# v0_6_1.net
KiCad netlist of a schematic drawn in EAGLE
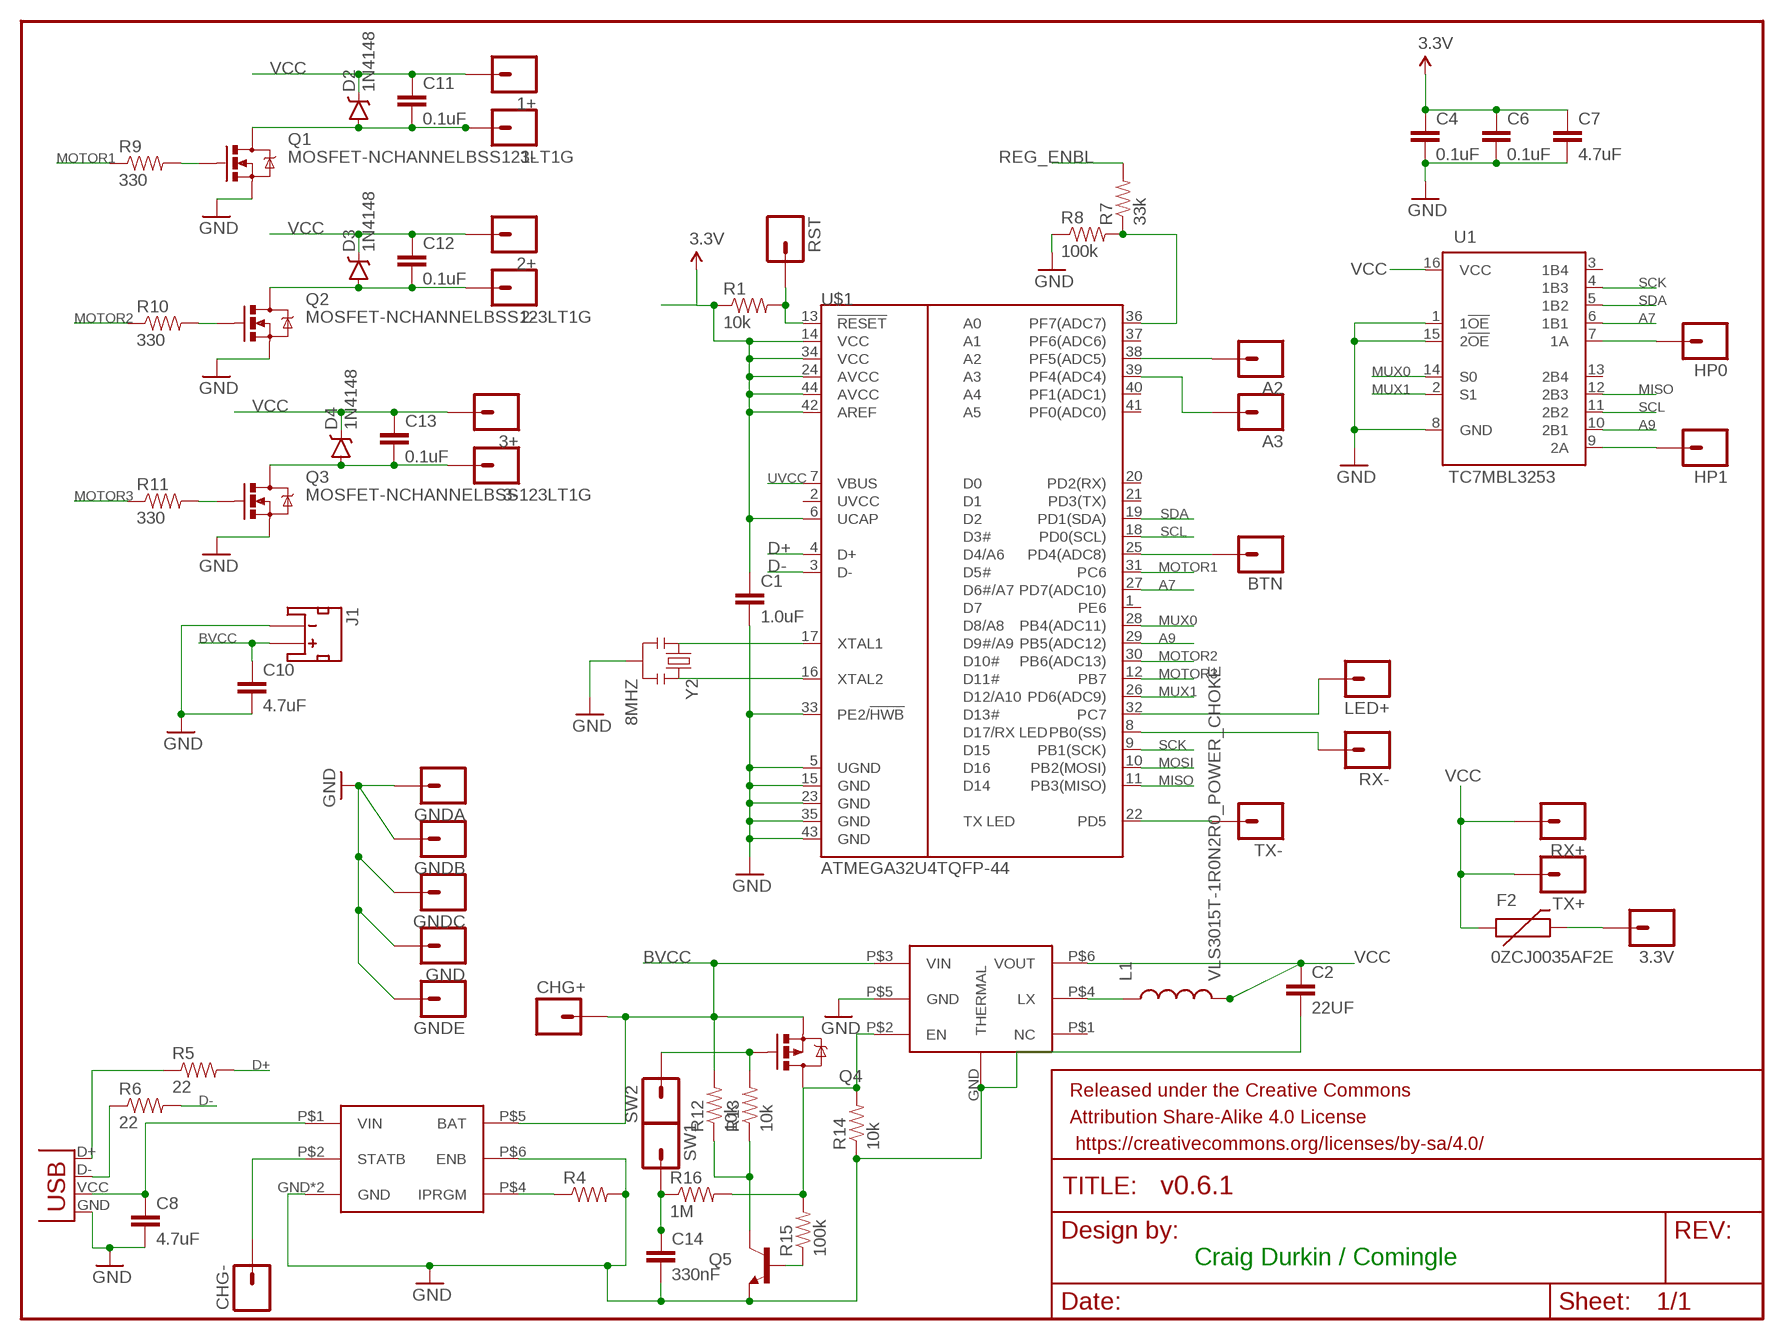
[diagram p0: schematic, sheet 1]

(export (version "E")
  (design (tool "Eeschema 10.0.6"))
  (components
    (comp (ref "1+")
      (value "M01PTH")
      (footprint "eagle-import:1X01")
      (libsource (lib "eagle-import") (part "M01PTH"))
    )
    (comp (ref "1-")
      (value "M01PTH")
      (footprint "eagle-import:1X01")
      (libsource (lib "eagle-import") (part "M01PTH"))
    )
    (comp (ref "2+")
      (value "M01PTH")
      (footprint "eagle-import:1X01")
      (libsource (lib "eagle-import") (part "M01PTH"))
    )
    (comp (ref "2-")
      (value "M01PTH")
      (footprint "eagle-import:1X01")
      (libsource (lib "eagle-import") (part "M01PTH"))
    )
    (comp (ref "3+")
      (value "M01PTH")
      (footprint "eagle-import:1X01")
      (libsource (lib "eagle-import") (part "M01PTH"))
    )
    (comp (ref "3-")
      (value "M01PTH")
      (footprint "eagle-import:1X01")
      (libsource (lib "eagle-import") (part "M01PTH"))
    )
    (comp (ref "3.3V")
      (value "M01PTH")
      (footprint "eagle-import:1X01")
      (libsource (lib "eagle-import") (part "M01PTH"))
    )
    (comp (ref "A2")
      (value "M01PTH")
      (footprint "eagle-import:1X01")
      (libsource (lib "eagle-import") (part "M01PTH"))
    )
    (comp (ref "A3")
      (value "M01PTH")
      (footprint "eagle-import:1X01")
      (libsource (lib "eagle-import") (part "M01PTH"))
    )
    (comp (ref "BTN")
      (value "M01PTH")
      (footprint "eagle-import:1X01")
      (libsource (lib "eagle-import") (part "M01PTH"))
    )
    (comp (ref "C1")
      (value "1.0uF")
      (footprint "eagle-import:0603-CAP")
      (libsource (lib "eagle-import") (part "CAP0603-CAP"))
    )
    (comp (ref "C2")
      (value "22UF")
      (footprint "eagle-import:0805")
      (libsource (lib "eagle-import") (part "v0.4.6_CAP0805"))
    )
    (comp (ref "C4")
      (value "0.1uF")
      (footprint "eagle-import:0603-CAP")
      (libsource (lib "eagle-import") (part "SparkFun-Passives_CAP0603-CAP"))
    )
    (comp (ref "C6")
      (value "0.1uF")
      (footprint "eagle-import:0603-CAP")
      (libsource (lib "eagle-import") (part "SparkFun-Passives_CAP0603-CAP"))
    )
    (comp (ref "C7")
      (value "4.7uF")
      (footprint "eagle-import:0603-CAP")
      (libsource (lib "eagle-import") (part "SparkFun-Passives_CAP0603-CAP"))
    )
    (comp (ref "C8")
      (value "4.7uF")
      (footprint "eagle-import:0603-CAP")
      (libsource (lib "eagle-import") (part "SparkFun-Passives_CAP0603-CAP"))
    )
    (comp (ref "C10")
      (value "4.7uF")
      (footprint "eagle-import:0603-CAP")
      (libsource (lib "eagle-import") (part "SparkFun-Passives_CAP0603-CAP"))
    )
    (comp (ref "C11")
      (value "0.1uF")
      (footprint "eagle-import:0603-CAP")
      (libsource (lib "eagle-import") (part "CAP0603-CAP"))
    )
    (comp (ref "C12")
      (value "0.1uF")
      (footprint "eagle-import:0603-CAP")
      (libsource (lib "eagle-import") (part "CAP0603-CAP"))
    )
    (comp (ref "C13")
      (value "0.1uF")
      (footprint "eagle-import:0603-CAP")
      (libsource (lib "eagle-import") (part "CAP0603-CAP"))
    )
    (comp (ref "C14")
      (value "330nF")
      (footprint "eagle-import:0603-CAP")
      (libsource (lib "eagle-import") (part "CAP0603-CAP"))
    )
    (comp (ref "CHG+")
      (value "M01PTH")
      (footprint "eagle-import:1X01")
      (libsource (lib "eagle-import") (part "M01PTH"))
    )
    (comp (ref "CHG-")
      (value "M01PTH")
      (footprint "eagle-import:1X01")
      (libsource (lib "eagle-import") (part "M01PTH"))
    )
    (comp (ref "D2")
      (value "1N4148")
      (footprint "eagle-import:SOD-323")
      (libsource (lib "eagle-import") (part "BAT20JFILM"))
    )
    (comp (ref "D3")
      (value "1N4148")
      (footprint "eagle-import:SOD-323")
      (libsource (lib "eagle-import") (part "BAT20JFILM"))
    )
    (comp (ref "D4")
      (value "1N4148")
      (footprint "eagle-import:SOD-323")
      (libsource (lib "eagle-import") (part "BAT20JFILM"))
    )
    (comp (ref "F2")
      (value "0ZCJ0035AF2E")
      (footprint "eagle-import:PTC-1206")
      (libsource (lib "eagle-import") (part "PTCSMD"))
    )
    (comp (ref "FRAME1")
      (value "FRAME-LETTER")
      (footprint "eagle-import:CREATIVE_COMMONS")
      (libsource (lib "eagle-import") (part "FRAME-LETTER"))
    )
    (comp (ref "GND")
      (value "M01PTH")
      (footprint "eagle-import:1X01")
      (libsource (lib "eagle-import") (part "M01PTH"))
    )
    (comp (ref "GNDA")
      (value "M01PTH")
      (footprint "eagle-import:1X01")
      (libsource (lib "eagle-import") (part "M01PTH"))
    )
    (comp (ref "GNDB")
      (value "M01PTH")
      (footprint "eagle-import:1X01")
      (libsource (lib "eagle-import") (part "M01PTH"))
    )
    (comp (ref "GNDC")
      (value "M01PTH")
      (footprint "eagle-import:1X01")
      (libsource (lib "eagle-import") (part "M01PTH"))
    )
    (comp (ref "GNDE")
      (value "M01PTH")
      (footprint "eagle-import:1X01")
      (libsource (lib "eagle-import") (part "M01PTH"))
    )
    (comp (ref "HP0")
      (value "M01PTH")
      (footprint "eagle-import:1X01")
      (libsource (lib "eagle-import") (part "M01PTH"))
    )
    (comp (ref "HP1")
      (value "M01PTH")
      (footprint "eagle-import:1X01")
      (libsource (lib "eagle-import") (part "M01PTH"))
    )
    (comp (ref "J1")
      (value "JST_2MM_MALE")
      (footprint "eagle-import:JST-2-SMD")
      (libsource (lib "eagle-import") (part "JST_2MM_MALE"))
    )
    (comp (ref "JP4")
      (value "USBMICROB-GCT-USB3075")
      (footprint "eagle-import:USB-MICROB-GCT-USB3075")
      (libsource (lib "eagle-import") (part "USBMICROB-GCT-USB3075"))
    )
    (comp (ref "L1")
      (value "VLS3015T-1R0N2R0_POWER_CHOKE")
      (footprint "eagle-import:3MM_POWER_CHOKE")
      (libsource (lib "eagle-import") (part "VLS3015T-1R0N2R0_POWER_CHOKE"))
    )
    (comp (ref "LED+")
      (value "M01PTH")
      (footprint "eagle-import:1X01")
      (libsource (lib "eagle-import") (part "M01PTH"))
    )
    (comp (ref "Q1")
      (value "MOSFET-NCHANNELBSS123LT1G")
      (footprint "eagle-import:SOT23-3")
      (libsource (lib "eagle-import") (part "MOSFET-NCHANNELBSS123LT1G"))
    )
    (comp (ref "Q2")
      (value "MOSFET-NCHANNELBSS123LT1G")
      (footprint "eagle-import:SOT23-3")
      (libsource (lib "eagle-import") (part "MOSFET-NCHANNELBSS123LT1G"))
    )
    (comp (ref "Q3")
      (value "MOSFET-NCHANNELBSS123LT1G")
      (footprint "eagle-import:SOT23-3")
      (libsource (lib "eagle-import") (part "MOSFET-NCHANNELBSS123LT1G"))
    )
    (comp (ref "Q4")
      (value "NTS2101PT1G")
      (footprint "eagle-import:SOT323")
      (libsource (lib "eagle-import") (part "MOSFET-PCHANNELSOT323"))
    )
    (comp (ref "Q5")
      (value "MMBT2222A")
      (footprint "eagle-import:SOT23-3")
      (libsource (lib "eagle-import") (part "TRANSISTOR_NPNMMBT2222A"))
    )
    (comp (ref "R1")
      (value "10k")
      (footprint "eagle-import:0603-RES")
      (libsource (lib "eagle-import") (part "RESISTOR0603-RES"))
    )
    (comp (ref "R4")
      (value "RESISTOR0603-RES")
      (footprint "eagle-import:0603-RES")
      (libsource (lib "eagle-import") (part "RESISTOR0603-RES"))
    )
    (comp (ref "R5")
      (value "22")
      (footprint "eagle-import:0603-RES")
      (libsource (lib "eagle-import") (part "RESISTOR0603-RES"))
    )
    (comp (ref "R6")
      (value "22")
      (footprint "eagle-import:0603-RES")
      (libsource (lib "eagle-import") (part "RESISTOR0603-RES"))
    )
    (comp (ref "R7")
      (value "33k")
      (footprint "eagle-import:0603-RES")
      (libsource (lib "eagle-import") (part "RESISTOR0603-RES"))
    )
    (comp (ref "R8")
      (value "100k")
      (footprint "eagle-import:0603-RES")
      (libsource (lib "eagle-import") (part "RESISTOR0603-RES"))
    )
    (comp (ref "R9")
      (value "330")
      (footprint "eagle-import:0603-RES")
      (libsource (lib "eagle-import") (part "RESISTOR0603-RES"))
    )
    (comp (ref "R10")
      (value "330")
      (footprint "eagle-import:0603-RES")
      (libsource (lib "eagle-import") (part "RESISTOR0603-RES"))
    )
    (comp (ref "R11")
      (value "330")
      (footprint "eagle-import:0603-RES")
      (libsource (lib "eagle-import") (part "RESISTOR0603-RES"))
    )
    (comp (ref "R12")
      (value "10k")
      (footprint "eagle-import:0603-RES")
      (libsource (lib "eagle-import") (part "RESISTOR0603-RES"))
    )
    (comp (ref "R13")
      (value "10k")
      (footprint "eagle-import:0603-RES")
      (libsource (lib "eagle-import") (part "RESISTOR0603-RES"))
    )
    (comp (ref "R14")
      (value "10k")
      (footprint "eagle-import:0603-RES")
      (libsource (lib "eagle-import") (part "RESISTOR0603-RES"))
    )
    (comp (ref "R15")
      (value "100k")
      (footprint "eagle-import:0603-RES")
      (libsource (lib "eagle-import") (part "RESISTOR0603-RES"))
    )
    (comp (ref "R16")
      (value "1M")
      (footprint "eagle-import:0603-RES")
      (libsource (lib "eagle-import") (part "RESISTOR0603-RES"))
    )
    (comp (ref "RST")
      (value "M01PTH")
      (footprint "eagle-import:1X01")
      (libsource (lib "eagle-import") (part "M01PTH"))
    )
    (comp (ref "RX+")
      (value "M01PTH")
      (footprint "eagle-import:1X01")
      (libsource (lib "eagle-import") (part "M01PTH"))
    )
    (comp (ref "RX-")
      (value "M01PTH")
      (footprint "eagle-import:1X01")
      (libsource (lib "eagle-import") (part "M01PTH"))
    )
    (comp (ref "SW1")
      (value "M01PTH")
      (footprint "eagle-import:1X01")
      (libsource (lib "eagle-import") (part "M01PTH"))
    )
    (comp (ref "SW2")
      (value "M01PTH")
      (footprint "eagle-import:1X01")
      (libsource (lib "eagle-import") (part "M01PTH"))
    )
    (comp (ref "TX+")
      (value "M01PTH")
      (footprint "eagle-import:1X01")
      (libsource (lib "eagle-import") (part "M01PTH"))
    )
    (comp (ref "TX-")
      (value "M01PTH")
      (footprint "eagle-import:1X01")
      (libsource (lib "eagle-import") (part "M01PTH"))
    )
    (comp (ref "U$1")
      (value "ATMEGA32U4TQFP-44")
      (footprint "eagle-import:TQFP44")
      (libsource (lib "eagle-import") (part "ATMEGA32U4TQFP-44"))
    )
    (comp (ref "U$3")
      (value "SC189")
      (footprint "eagle-import:MLPD-UT6")
      (libsource (lib "eagle-import") (part "SC189"))
    )
    (comp (ref "U$4")
      (value "SC810")
      (footprint "eagle-import:MLPD-UT6")
      (libsource (lib "eagle-import") (part "SC810"))
    )
    (comp (ref "U1")
      (value "TC7MBL3253")
      (footprint "eagle-import:SSOP16")
      (libsource (lib "eagle-import") (part "TC7MBL3253"))
    )
    (comp (ref "Y2")
      (value "8MHZ")
      (footprint "eagle-import:RESONATOR-SMD")
      (libsource (lib "eagle-import") (part "RESONATOR8MHZ"))
    )
  )
  (nets
    (net (code "1") (name "/A7") (class "Default")
      (node (ref "U$1") (pin "27") (pinfunction "PD7(ADC10)_27") (pintype "bidirectional"))
      (node (ref "U1") (pin "6") (pinfunction "1B1_6") (pintype "bidirectional"))
    )
    (net (code "2") (name "/A9") (class "Default")
      (node (ref "U$1") (pin "29") (pinfunction "PB5(ADC12)_29") (pintype "bidirectional"))
      (node (ref "U1") (pin "10") (pinfunction "2B1_10") (pintype "bidirectional"))
    )
    (net (code "3") (name "/BVCC") (class "Default")
      (node (ref "C10") (pin "1") (pinfunction "1_1") (pintype "passive"))
      (node (ref "CHG+") (pin "1") (pinfunction "1_1") (pintype "passive"))
      (node (ref "J1") (pin "2") (pinfunction "+_2") (pintype "bidirectional"))
      (node (ref "Q4") (pin "2") (pinfunction "S_2") (pintype "passive"))
      (node (ref "R12") (pin "2") (pinfunction "2_2") (pintype "passive"))
      (node (ref "U$3") (pin "P$3") (pinfunction "VIN_P$3") (pintype "power_in"))
      (node (ref "U$4") (pin "P$5") (pinfunction "BAT_P$5") (pintype "output"))
    )
    (net (code "4") (name "/D+") (class "Default")
      (node (ref "R5") (pin "2") (pinfunction "2_2") (pintype "passive"))
      (node (ref "U$1") (pin "4") (pinfunction "D+_4") (pintype "bidirectional"))
    )
    (net (code "5") (name "/D-") (class "Default")
      (node (ref "R6") (pin "2") (pinfunction "2_2") (pintype "passive"))
      (node (ref "U$1") (pin "3") (pinfunction "D-_3") (pintype "bidirectional"))
    )
    (net (code "6") (name "/MISO") (class "Default")
      (node (ref "U$1") (pin "11") (pinfunction "PB3(MISO)_11") (pintype "bidirectional"))
      (node (ref "U1") (pin "12") (pinfunction "2B3_12") (pintype "bidirectional"))
    )
    (net (code "7") (name "/MOSI") (class "Default")
      (node (ref "U$1") (pin "10") (pinfunction "PB2(MOSI)_10") (pintype "bidirectional"))
    )
    (net (code "8") (name "/MOTOR1") (class "Default")
      (node (ref "R9") (pin "1") (pinfunction "1_1") (pintype "passive"))
      (node (ref "U$1") (pin "31") (pinfunction "PC6_31") (pintype "bidirectional"))
    )
    (net (code "9") (name "/MOTOR2") (class "Default")
      (node (ref "R10") (pin "1") (pinfunction "1_1") (pintype "passive"))
      (node (ref "U$1") (pin "30") (pinfunction "PB6(ADC13)_30") (pintype "bidirectional"))
    )
    (net (code "10") (name "/MOTOR3") (class "Default")
      (node (ref "R11") (pin "1") (pinfunction "1_1") (pintype "passive"))
      (node (ref "U$1") (pin "12") (pinfunction "PB7_12") (pintype "bidirectional"))
    )
    (net (code "11") (name "/MUX0") (class "Default")
      (node (ref "U$1") (pin "28") (pinfunction "PB4(ADC11)_28") (pintype "bidirectional"))
      (node (ref "U1") (pin "14") (pinfunction "S0_14") (pintype "bidirectional"))
    )
    (net (code "12") (name "/MUX1") (class "Default")
      (node (ref "U$1") (pin "26") (pinfunction "PD6(ADC9)_26") (pintype "bidirectional"))
      (node (ref "U1") (pin "2") (pinfunction "S1_2") (pintype "bidirectional"))
    )
    (net (code "13") (name "/REG_ENBL") (class "Default")
      (node (ref "Q4") (pin "3") (pinfunction "D_3") (pintype "passive"))
      (node (ref "R14") (pin "2") (pinfunction "2_2") (pintype "passive"))
      (node (ref "R15") (pin "2") (pinfunction "2_2") (pintype "passive"))
      (node (ref "R16") (pin "2") (pinfunction "2_2") (pintype "passive"))
      (node (ref "R7") (pin "2") (pinfunction "2_2") (pintype "passive"))
      (node (ref "U$3") (pin "P$2") (pinfunction "EN_P$2") (pintype "input"))
    )
    (net (code "14") (name "/SCK") (class "Default")
      (node (ref "U$1") (pin "9") (pinfunction "PB1(SCK)_9") (pintype "bidirectional"))
      (node (ref "U1") (pin "4") (pinfunction "1B3_4") (pintype "bidirectional"))
    )
    (net (code "15") (name "/SCL") (class "Default")
      (node (ref "U$1") (pin "18") (pinfunction "PD0(SCL)_18") (pintype "bidirectional"))
      (node (ref "U1") (pin "11") (pinfunction "2B2_11") (pintype "bidirectional"))
    )
    (net (code "16") (name "/SDA") (class "Default")
      (node (ref "U$1") (pin "19") (pinfunction "PD1(SDA)_19") (pintype "bidirectional"))
      (node (ref "U1") (pin "5") (pinfunction "1B2_5") (pintype "bidirectional"))
    )
    (net (code "17") (name "/UVCC") (class "Default")
      (node (ref "C8") (pin "1") (pinfunction "1_1") (pintype "passive"))
      (node (ref "JP4") (pin "VCC") (pinfunction "VBUS_VCC") (pintype "bidirectional"))
      (node (ref "U$1") (pin "7") (pinfunction "VBUS_7") (pintype "bidirectional"))
      (node (ref "U$4") (pin "P$1") (pinfunction "VIN_P$1") (pintype "power_in"))
    )
    (net (code "18") (name "3.3V") (class "Default")
      (node (ref "1+") (pin "1") (pinfunction "1_1") (pintype "passive"))
      (node (ref "2+") (pin "1") (pinfunction "1_1") (pintype "passive"))
      (node (ref "3+") (pin "1") (pinfunction "1_1") (pintype "passive"))
      (node (ref "C1") (pin "1") (pinfunction "1_1") (pintype "passive"))
      (node (ref "C11") (pin "1") (pinfunction "1_1") (pintype "passive"))
      (node (ref "C12") (pin "1") (pinfunction "1_1") (pintype "passive"))
      (node (ref "C13") (pin "1") (pinfunction "1_1") (pintype "passive"))
      (node (ref "C2") (pin "1") (pinfunction "1_1") (pintype "passive"))
      (node (ref "C4") (pin "1") (pinfunction "1_1") (pintype "passive"))
      (node (ref "C6") (pin "1") (pinfunction "1_1") (pintype "passive"))
      (node (ref "C7") (pin "1") (pinfunction "1_1") (pintype "passive"))
      (node (ref "D2") (pin "C") (pinfunction "C_C") (pintype "passive"))
      (node (ref "D3") (pin "C") (pinfunction "C_C") (pintype "passive"))
      (node (ref "D4") (pin "C") (pinfunction "C_C") (pintype "passive"))
      (node (ref "F2") (pin "1") (pinfunction "1_1") (pintype "bidirectional"))
      (node (ref "L1") (pin "2") (pinfunction "2_2") (pintype "passive"))
      (node (ref "R1") (pin "1") (pinfunction "1_1") (pintype "passive"))
      (node (ref "RX+") (pin "1") (pinfunction "1_1") (pintype "passive"))
      (node (ref "TX+") (pin "1") (pinfunction "1_1") (pintype "passive"))
      (node (ref "U$1") (pin "14") (pinfunction "VCC_14") (pintype "bidirectional"))
      (node (ref "U$1") (pin "24") (pinfunction "AVCC_24") (pintype "bidirectional"))
      (node (ref "U$1") (pin "34") (pinfunction "VCC_34") (pintype "bidirectional"))
      (node (ref "U$1") (pin "42") (pinfunction "AREF_42") (pintype "bidirectional"))
      (node (ref "U$1") (pin "44") (pinfunction "AVCC_44") (pintype "bidirectional"))
      (node (ref "U$1") (pin "6") (pinfunction "UCAP_6") (pintype "bidirectional"))
      (node (ref "U$3") (pin "P$6") (pinfunction "VOUT_P$6") (pintype "output"))
      (node (ref "U1") (pin "16") (pinfunction "VCC_16") (pintype "power_in"))
    )
    (net (code "19") (name "GND") (class "Default")
      (node (ref "C1") (pin "2") (pinfunction "2_2") (pintype "passive"))
      (node (ref "C10") (pin "2") (pinfunction "2_2") (pintype "passive"))
      (node (ref "C14") (pin "2") (pinfunction "2_2") (pintype "passive"))
      (node (ref "C2") (pin "2") (pinfunction "2_2") (pintype "passive"))
      (node (ref "C4") (pin "2") (pinfunction "2_2") (pintype "passive"))
      (node (ref "C6") (pin "2") (pinfunction "2_2") (pintype "passive"))
      (node (ref "C7") (pin "2") (pinfunction "2_2") (pintype "passive"))
      (node (ref "C8") (pin "2") (pinfunction "2_2") (pintype "passive"))
      (node (ref "GND") (pin "1") (pinfunction "1_1") (pintype "passive"))
      (node (ref "GNDA") (pin "1") (pinfunction "1_1") (pintype "passive"))
      (node (ref "GNDB") (pin "1") (pinfunction "1_1") (pintype "passive"))
      (node (ref "GNDC") (pin "1") (pinfunction "1_1") (pintype "passive"))
      (node (ref "GNDE") (pin "1") (pinfunction "1_1") (pintype "passive"))
      (node (ref "J1") (pin "1") (pinfunction "-_1") (pintype "bidirectional"))
      (node (ref "JP4") (pin "GND") (pinfunction "GND_GND") (pintype "bidirectional"))
      (node (ref "Q1") (pin "2") (pinfunction "S_2") (pintype "passive"))
      (node (ref "Q2") (pin "2") (pinfunction "S_2") (pintype "passive"))
      (node (ref "Q3") (pin "2") (pinfunction "S_2") (pintype "passive"))
      (node (ref "Q5") (pin "2") (pinfunction "E_2") (pintype "passive"))
      (node (ref "R14") (pin "1") (pinfunction "1_1") (pintype "passive"))
      (node (ref "R4") (pin "2") (pinfunction "2_2") (pintype "passive"))
      (node (ref "R8") (pin "1") (pinfunction "1_1") (pintype "passive"))
      (node (ref "U$1") (pin "15") (pinfunction "GND_15") (pintype "bidirectional"))
      (node (ref "U$1") (pin "23") (pinfunction "GND_23") (pintype "bidirectional"))
      (node (ref "U$1") (pin "33") (pinfunction "PE2/~{HWB}_33") (pintype "bidirectional"))
      (node (ref "U$1") (pin "35") (pinfunction "GND_35") (pintype "bidirectional"))
      (node (ref "U$1") (pin "43") (pinfunction "GND_43") (pintype "bidirectional"))
      (node (ref "U$1") (pin "5") (pinfunction "UGND_5") (pintype "bidirectional"))
      (node (ref "U$3") (pin "GND") (pinfunction "THERMAL_GND") (pintype "power_in"))
      (node (ref "U$3") (pin "P$5") (pinfunction "GND_P$5") (pintype "power_in"))
      (node (ref "U$4") (pin "GND") (pinfunction "GND_GND") (pintype "power_in"))
      (node (ref "U$4") (pin "P$3") (pinfunction "GND_P$3") (pintype "power_in"))
      (node (ref "U$4") (pin "P$6") (pinfunction "ENB_P$6") (pintype "bidirectional"))
      (node (ref "U1") (pin "1") (pinfunction "1~{OE}_1") (pintype "input"))
      (node (ref "U1") (pin "15") (pinfunction "2~{OE}_15") (pintype "input"))
      (node (ref "U1") (pin "8") (pinfunction "GND_8") (pintype "power_in"))
      (node (ref "Y2") (pin "2") (pinfunction "2_2") (pintype "passive"))
    )
    (net (code "20") (name "Net-(3.3V-Pad1)") (class "Default")
      (node (ref "3.3V") (pin "1") (pinfunction "1_1") (pintype "passive"))
      (node (ref "F2") (pin "2") (pinfunction "2_2") (pintype "bidirectional"))
    )
    (net (code "21") (name "Net-(C14-Pad1)") (class "Default")
      (node (ref "C14") (pin "1") (pinfunction "1_1") (pintype "passive"))
      (node (ref "R16") (pin "1") (pinfunction "1_1") (pintype "passive"))
      (node (ref "SW1") (pin "1") (pinfunction "1_1") (pintype "passive"))
    )
    (net (code "22") (name "Net-(JP4-PadD+)") (class "Default")
      (node (ref "JP4") (pin "D+") (pinfunction "D+_D+") (pintype "bidirectional"))
      (node (ref "R5") (pin "1") (pinfunction "1_1") (pintype "passive"))
    )
    (net (code "23") (name "Net-(JP4-PadD-)") (class "Default")
      (node (ref "JP4") (pin "D-") (pinfunction "D-_D-") (pintype "bidirectional"))
      (node (ref "R6") (pin "1") (pinfunction "1_1") (pintype "passive"))
    )
    (net (code "24") (name "Net-(Q1-D)") (class "Default")
      (node (ref "1-") (pin "1") (pinfunction "1_1") (pintype "passive"))
      (node (ref "C11") (pin "2") (pinfunction "2_2") (pintype "passive"))
      (node (ref "D2") (pin "A") (pinfunction "A_A") (pintype "passive"))
      (node (ref "Q1") (pin "3") (pinfunction "D_3") (pintype "passive"))
    )
    (net (code "25") (name "Net-(Q1-G)") (class "Default")
      (node (ref "Q1") (pin "1") (pinfunction "G_1") (pintype "passive"))
      (node (ref "R9") (pin "2") (pinfunction "2_2") (pintype "passive"))
    )
    (net (code "26") (name "Net-(Q2-D)") (class "Default")
      (node (ref "2-") (pin "1") (pinfunction "1_1") (pintype "passive"))
      (node (ref "C12") (pin "2") (pinfunction "2_2") (pintype "passive"))
      (node (ref "D3") (pin "A") (pinfunction "A_A") (pintype "passive"))
      (node (ref "Q2") (pin "3") (pinfunction "D_3") (pintype "passive"))
    )
    (net (code "27") (name "Net-(Q2-G)") (class "Default")
      (node (ref "Q2") (pin "1") (pinfunction "G_1") (pintype "passive"))
      (node (ref "R10") (pin "2") (pinfunction "2_2") (pintype "passive"))
    )
    (net (code "28") (name "Net-(Q3-D)") (class "Default")
      (node (ref "3-") (pin "1") (pinfunction "1_1") (pintype "passive"))
      (node (ref "C13") (pin "2") (pinfunction "2_2") (pintype "passive"))
      (node (ref "D4") (pin "A") (pinfunction "A_A") (pintype "passive"))
      (node (ref "Q3") (pin "3") (pinfunction "D_3") (pintype "passive"))
    )
    (net (code "29") (name "Net-(Q3-G)") (class "Default")
      (node (ref "Q3") (pin "1") (pinfunction "G_1") (pintype "passive"))
      (node (ref "R11") (pin "2") (pinfunction "2_2") (pintype "passive"))
    )
    (net (code "30") (name "Net-(Q4-G)") (class "Default")
      (node (ref "Q4") (pin "1") (pinfunction "G_1") (pintype "passive"))
      (node (ref "R13") (pin "2") (pinfunction "2_2") (pintype "passive"))
      (node (ref "SW2") (pin "1") (pinfunction "1_1") (pintype "passive"))
    )
    (net (code "31") (name "Net-(Q5-B)") (class "Default")
      (node (ref "Q5") (pin "1") (pinfunction "B_1") (pintype "passive"))
      (node (ref "R15") (pin "1") (pinfunction "1_1") (pintype "passive"))
    )
    (net (code "32") (name "Net-(Q5-C)") (class "Default")
      (node (ref "Q5") (pin "3") (pinfunction "C_3") (pintype "passive"))
      (node (ref "R12") (pin "1") (pinfunction "1_1") (pintype "passive"))
      (node (ref "R13") (pin "1") (pinfunction "1_1") (pintype "passive"))
    )
    (net (code "33") (name "Net-(U$1-PB0(SS))") (class "Default")
      (node (ref "RX-") (pin "1") (pinfunction "1_1") (pintype "passive"))
      (node (ref "U$1") (pin "8") (pinfunction "PB0(SS)_8") (pintype "bidirectional"))
    )
    (net (code "34") (name "Net-(U$1-PC7)") (class "Default")
      (node (ref "LED+") (pin "1") (pinfunction "1_1") (pintype "passive"))
      (node (ref "U$1") (pin "32") (pinfunction "PC7_32") (pintype "bidirectional"))
    )
    (net (code "35") (name "Net-(U$1-PD4(ADC8))") (class "Default")
      (node (ref "BTN") (pin "1") (pinfunction "1_1") (pintype "passive"))
      (node (ref "U$1") (pin "25") (pinfunction "PD4(ADC8)_25") (pintype "bidirectional"))
    )
    (net (code "36") (name "Net-(U$1-PD5)") (class "Default")
      (node (ref "TX-") (pin "1") (pinfunction "1_1") (pintype "passive"))
      (node (ref "U$1") (pin "22") (pinfunction "PD5_22") (pintype "bidirectional"))
    )
    (net (code "37") (name "Net-(U$1-PF4(ADC4))") (class "Default")
      (node (ref "A3") (pin "1") (pinfunction "1_1") (pintype "passive"))
      (node (ref "U$1") (pin "39") (pinfunction "PF4(ADC4)_39") (pintype "bidirectional"))
    )
    (net (code "38") (name "Net-(U$1-PF5(ADC5))") (class "Default")
      (node (ref "A2") (pin "1") (pinfunction "1_1") (pintype "passive"))
      (node (ref "U$1") (pin "38") (pinfunction "PF5(ADC5)_38") (pintype "bidirectional"))
    )
    (net (code "39") (name "Net-(U$1-PF7(ADC7))") (class "Default")
      (node (ref "R7") (pin "1") (pinfunction "1_1") (pintype "passive"))
      (node (ref "R8") (pin "2") (pinfunction "2_2") (pintype "passive"))
      (node (ref "U$1") (pin "36") (pinfunction "PF7(ADC7)_36") (pintype "bidirectional"))
    )
    (net (code "40") (name "Net-(U$1-XTAL1)") (class "Default")
      (node (ref "U$1") (pin "17") (pinfunction "XTAL1_17") (pintype "bidirectional"))
      (node (ref "Y2") (pin "1") (pinfunction "1_1") (pintype "passive"))
    )
    (net (code "41") (name "Net-(U$1-XTAL2)") (class "Default")
      (node (ref "U$1") (pin "16") (pinfunction "XTAL2_16") (pintype "bidirectional"))
      (node (ref "Y2") (pin "3") (pinfunction "3_3") (pintype "passive"))
    )
    (net (code "42") (name "Net-(U$1-~{RESET})") (class "Default")
      (node (ref "R1") (pin "2") (pinfunction "2_2") (pintype "passive"))
      (node (ref "RST") (pin "1") (pinfunction "1_1") (pintype "passive"))
      (node (ref "U$1") (pin "13") (pinfunction "~{RESET}_13") (pintype "bidirectional"))
    )
    (net (code "43") (name "Net-(U$3-LX)") (class "Default")
      (node (ref "L1") (pin "1") (pinfunction "1_1") (pintype "passive"))
      (node (ref "U$3") (pin "P$4") (pinfunction "LX_P$4") (pintype "passive"))
    )
    (net (code "44") (name "Net-(U$4-IPRGM)") (class "Default")
      (node (ref "R4") (pin "1") (pinfunction "1_1") (pintype "passive"))
      (node (ref "U$4") (pin "P$4") (pinfunction "IPRGM_P$4") (pintype "bidirectional"))
    )
    (net (code "45") (name "Net-(U$4-STATB)") (class "Default")
      (node (ref "CHG-") (pin "1") (pinfunction "1_1") (pintype "passive"))
      (node (ref "U$4") (pin "P$2") (pinfunction "STATB_P$2") (pintype "bidirectional"))
    )
    (net (code "46") (name "Net-(U1-1A)") (class "Default")
      (node (ref "HP0") (pin "1") (pinfunction "1_1") (pintype "passive"))
      (node (ref "U1") (pin "7") (pinfunction "1A_7") (pintype "bidirectional"))
    )
    (net (code "47") (name "Net-(U1-2A)") (class "Default")
      (node (ref "HP1") (pin "1") (pinfunction "1_1") (pintype "passive"))
      (node (ref "U1") (pin "9") (pinfunction "2A_9") (pintype "bidirectional"))
    )
    (net (code "48") (name "unconnected-(J1-PAD1-PadNC1)") (class "Default")
      (node (ref "J1") (pin "NC1") (pinfunction "PAD1_NC1") (pintype "bidirectional"))
    )
    (net (code "49") (name "unconnected-(J1-PAD2-PadNC2)") (class "Default")
      (node (ref "J1") (pin "NC2") (pinfunction "PAD2_NC2") (pintype "bidirectional"))
    )
    (net (code "50") (name "unconnected-(U$1-PD2(RX)-Pad20)") (class "Default")
      (node (ref "U$1") (pin "20") (pinfunction "PD2(RX)_20") (pintype "bidirectional"))
    )
    (net (code "51") (name "unconnected-(U$1-PD3(TX)-Pad21)") (class "Default")
      (node (ref "U$1") (pin "21") (pinfunction "PD3(TX)_21") (pintype "bidirectional"))
    )
    (net (code "52") (name "unconnected-(U$1-PE6-Pad1)") (class "Default")
      (node (ref "U$1") (pin "1") (pinfunction "PE6_1") (pintype "bidirectional"))
    )
    (net (code "53") (name "unconnected-(U$1-PF0(ADC0)-Pad41)") (class "Default")
      (node (ref "U$1") (pin "41") (pinfunction "PF0(ADC0)_41") (pintype "bidirectional"))
    )
    (net (code "54") (name "unconnected-(U$1-PF1(ADC1)-Pad40)") (class "Default")
      (node (ref "U$1") (pin "40") (pinfunction "PF1(ADC1)_40") (pintype "bidirectional"))
    )
    (net (code "55") (name "unconnected-(U$1-PF6(ADC6)-Pad37)") (class "Default")
      (node (ref "U$1") (pin "37") (pinfunction "PF6(ADC6)_37") (pintype "bidirectional"))
    )
    (net (code "56") (name "unconnected-(U$1-UVCC-Pad2)") (class "Default")
      (node (ref "U$1") (pin "2") (pinfunction "UVCC_2") (pintype "bidirectional"))
    )
    (net (code "57") (name "unconnected-(U$3-NC-PadP$1)") (class "Default")
      (node (ref "U$3") (pin "P$1") (pinfunction "NC_P$1") (pintype "no_connect"))
    )
    (net (code "58") (name "unconnected-(U1-1B4-Pad3)") (class "Default")
      (node (ref "U1") (pin "3") (pinfunction "1B4_3") (pintype "bidirectional"))
    )
    (net (code "59") (name "unconnected-(U1-2B4-Pad13)") (class "Default")
      (node (ref "U1") (pin "13") (pinfunction "2B4_13") (pintype "bidirectional"))
    )
  )
)
